# nRF2401A-Chip-v11.net
KiCad netlist of a schematic drawn in EAGLE
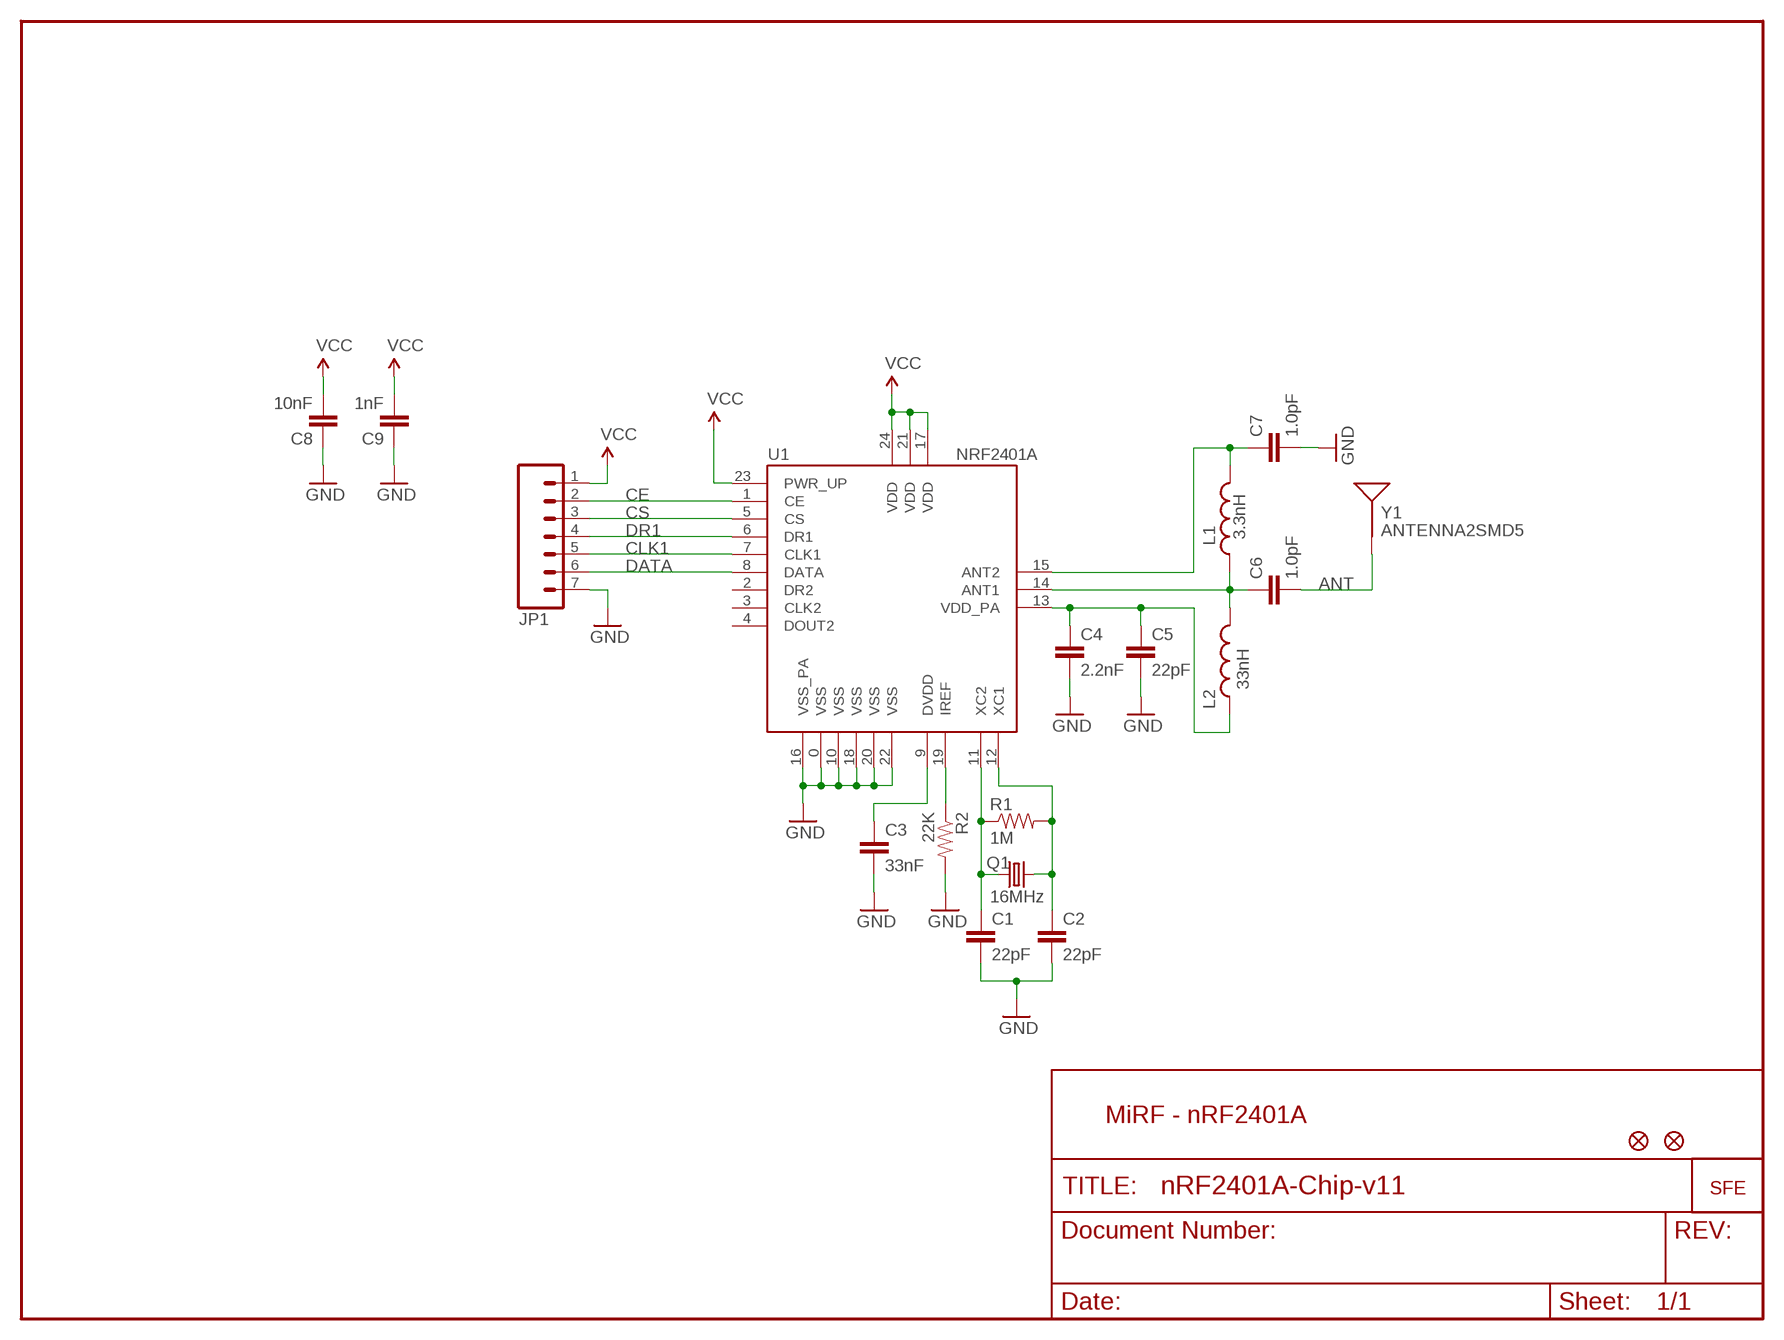
[diagram p0: schematic, sheet 1]

(export (version "E")
  (design (tool "Eeschema 10.0.6"))
  (components
    (comp (ref "C1")
      (value "22pF")
      (footprint "eagle-import:C0402")
      (libsource (lib "eagle-import") (part "CAP0402"))
    )
    (comp (ref "C2")
      (value "22pF")
      (footprint "eagle-import:C0402")
      (libsource (lib "eagle-import") (part "CAP0402"))
    )
    (comp (ref "C3")
      (value "33nF")
      (footprint "eagle-import:C0402")
      (libsource (lib "eagle-import") (part "CAP0402"))
    )
    (comp (ref "C4")
      (value "2.2nF")
      (footprint "eagle-import:C0402")
      (libsource (lib "eagle-import") (part "CAP0402"))
    )
    (comp (ref "C5")
      (value "22pF")
      (footprint "eagle-import:C0402")
      (libsource (lib "eagle-import") (part "CAP0402"))
    )
    (comp (ref "C6")
      (value "1.0pF")
      (footprint "eagle-import:C0402")
      (libsource (lib "eagle-import") (part "CAP0402"))
    )
    (comp (ref "C7")
      (value "1.0pF")
      (footprint "eagle-import:C0402")
      (libsource (lib "eagle-import") (part "CAP0402"))
    )
    (comp (ref "C8")
      (value "10nF")
      (footprint "eagle-import:C0402")
      (libsource (lib "eagle-import") (part "CAP0402"))
    )
    (comp (ref "C9")
      (value "1nF")
      (footprint "eagle-import:C0402")
      (libsource (lib "eagle-import") (part "CAP0402"))
    )
    (comp (ref "JP1")
      (value "M07")
      (footprint "eagle-import:1X07")
      (libsource (lib "eagle-import") (part "M07"))
    )
    (comp (ref "JP2")
      (value "FIDUCIALUFIDUCIAL")
      (footprint "eagle-import:MICRO-FIDUCIAL")
      (libsource (lib "eagle-import") (part "FIDUCIALUFIDUCIAL"))
    )
    (comp (ref "JP3")
      (value "FIDUCIALUFIDUCIAL")
      (footprint "eagle-import:MICRO-FIDUCIAL")
      (libsource (lib "eagle-import") (part "FIDUCIALUFIDUCIAL"))
    )
    (comp (ref "L1")
      (value "3.3nH")
      (footprint "eagle-import:C0402")
      (libsource (lib "eagle-import") (part "INDUCTOR0402"))
    )
    (comp (ref "L2")
      (value "33nH")
      (footprint "eagle-import:C0402")
      (libsource (lib "eagle-import") (part "INDUCTOR0402"))
    )
    (comp (ref "Q1")
      (value "16MHz")
      (footprint "eagle-import:CRYSTAL-SMD-5X3")
      (libsource (lib "eagle-import") (part "CRYSTAL5X3"))
    )
    (comp (ref "R1")
      (value "1M")
      (footprint "eagle-import:C0402")
      (libsource (lib "eagle-import") (part "RESISTOR0402"))
    )
    (comp (ref "R2")
      (value "22K")
      (footprint "eagle-import:C0402")
      (libsource (lib "eagle-import") (part "RESISTOR0402"))
    )
    (comp (ref "U$1")
      (value "LOGO-SFESK")
      (footprint "eagle-import:SFE-LOGO-FLAME")
      (libsource (lib "eagle-import") (part "LOGO-SFESK"))
    )
    (comp (ref "U1")
      (value "NRF2401A")
      (footprint "eagle-import:MLP-24")
      (libsource (lib "eagle-import") (part "NRF2401ASMD"))
    )
    (comp (ref "Y1")
      (value "ANTENNA2SMD5")
      (footprint "eagle-import:ANTENNA-CHIP5")
      (libsource (lib "eagle-import") (part "ANTENNA2SMD5"))
    )
  )
  (nets
    (net (code "1") (name "/ANT") (class "Default")
      (node (ref "C6") (pin "2") (pinfunction "2_2") (pintype "passive"))
      (node (ref "Y1") (pin "FEED") (pinfunction "SIGNAL_FEED") (pintype "bidirectional"))
    )
    (net (code "2") (name "/CE") (class "Default")
      (node (ref "JP1") (pin "2") (pinfunction "2_2") (pintype "passive"))
      (node (ref "U1") (pin "1") (pinfunction "CE_1") (pintype "input"))
    )
    (net (code "3") (name "/CLK1") (class "Default")
      (node (ref "JP1") (pin "5") (pinfunction "5_5") (pintype "passive"))
      (node (ref "U1") (pin "7") (pinfunction "CLK1_7") (pintype "bidirectional"))
    )
    (net (code "4") (name "/CS") (class "Default")
      (node (ref "JP1") (pin "3") (pinfunction "3_3") (pintype "passive"))
      (node (ref "U1") (pin "5") (pinfunction "CS_5") (pintype "input"))
    )
    (net (code "5") (name "/DATA") (class "Default")
      (node (ref "JP1") (pin "6") (pinfunction "6_6") (pintype "passive"))
      (node (ref "U1") (pin "8") (pinfunction "DATA_8") (pintype "bidirectional"))
    )
    (net (code "6") (name "/DR1") (class "Default")
      (node (ref "JP1") (pin "4") (pinfunction "4_4") (pintype "passive"))
      (node (ref "U1") (pin "6") (pinfunction "DR1_6") (pintype "output"))
    )
    (net (code "7") (name "GND") (class "Default")
      (node (ref "C1") (pin "2") (pinfunction "2_2") (pintype "passive"))
      (node (ref "C2") (pin "2") (pinfunction "2_2") (pintype "passive"))
      (node (ref "C3") (pin "2") (pinfunction "2_2") (pintype "passive"))
      (node (ref "C4") (pin "2") (pinfunction "2_2") (pintype "passive"))
      (node (ref "C5") (pin "2") (pinfunction "2_2") (pintype "passive"))
      (node (ref "C7") (pin "2") (pinfunction "2_2") (pintype "passive"))
      (node (ref "C8") (pin "1") (pinfunction "1_1") (pintype "passive"))
      (node (ref "C9") (pin "1") (pinfunction "1_1") (pintype "passive"))
      (node (ref "JP1") (pin "7") (pinfunction "7_7") (pintype "passive"))
      (node (ref "R2") (pin "2") (pinfunction "2_2") (pintype "passive"))
      (node (ref "U1") (pin "0") (pinfunction "VSS_0") (pintype "power_in"))
      (node (ref "U1") (pin "10") (pinfunction "VSS_10") (pintype "power_in"))
      (node (ref "U1") (pin "16") (pinfunction "VSS_PA_16") (pintype "power_in"))
      (node (ref "U1") (pin "18") (pinfunction "VSS_18") (pintype "power_in"))
      (node (ref "U1") (pin "20") (pinfunction "VSS_20") (pintype "power_in"))
      (node (ref "U1") (pin "22") (pinfunction "VSS_22") (pintype "power_in"))
    )
    (net (code "8") (name "Net-(Q1-2)") (class "Default")
      (node (ref "C2") (pin "1") (pinfunction "1_1") (pintype "passive"))
      (node (ref "Q1") (pin "3") (pinfunction "2_3") (pintype "passive"))
      (node (ref "R1") (pin "2") (pinfunction "2_2") (pintype "passive"))
      (node (ref "U1") (pin "12") (pinfunction "XC1_12") (pintype "input"))
    )
    (net (code "9") (name "Net-(U1-ANT1)") (class "Default")
      (node (ref "C6") (pin "1") (pinfunction "1_1") (pintype "passive"))
      (node (ref "L1") (pin "1") (pinfunction "1_1") (pintype "passive"))
      (node (ref "L2") (pin "2") (pinfunction "2_2") (pintype "passive"))
      (node (ref "U1") (pin "14") (pinfunction "ANT1_14") (pintype "output"))
    )
    (net (code "10") (name "Net-(U1-ANT2)") (class "Default")
      (node (ref "C7") (pin "1") (pinfunction "1_1") (pintype "passive"))
      (node (ref "L1") (pin "2") (pinfunction "2_2") (pintype "passive"))
      (node (ref "U1") (pin "15") (pinfunction "ANT2_15") (pintype "output"))
    )
    (net (code "11") (name "Net-(U1-DVDD)") (class "Default")
      (node (ref "C3") (pin "1") (pinfunction "1_1") (pintype "passive"))
      (node (ref "U1") (pin "9") (pinfunction "DVDD_9") (pintype "power_in"))
    )
    (net (code "12") (name "Net-(U1-IREF)") (class "Default")
      (node (ref "R2") (pin "1") (pinfunction "1_1") (pintype "passive"))
      (node (ref "U1") (pin "19") (pinfunction "IREF_19") (pintype "input"))
    )
    (net (code "13") (name "Net-(U1-VDD_PA)") (class "Default")
      (node (ref "C4") (pin "1") (pinfunction "1_1") (pintype "passive"))
      (node (ref "C5") (pin "1") (pinfunction "1_1") (pintype "passive"))
      (node (ref "L2") (pin "1") (pinfunction "1_1") (pintype "passive"))
      (node (ref "U1") (pin "13") (pinfunction "VDD_PA_13") (pintype "power_in"))
    )
    (net (code "14") (name "Net-(U1-XC2)") (class "Default")
      (node (ref "C1") (pin "1") (pinfunction "1_1") (pintype "passive"))
      (node (ref "Q1") (pin "1") (pinfunction "1_1") (pintype "passive"))
      (node (ref "R1") (pin "1") (pinfunction "1_1") (pintype "passive"))
      (node (ref "U1") (pin "11") (pinfunction "XC2_11") (pintype "input"))
    )
    (net (code "15") (name "VCC") (class "Default")
      (node (ref "C8") (pin "2") (pinfunction "2_2") (pintype "passive"))
      (node (ref "C9") (pin "2") (pinfunction "2_2") (pintype "passive"))
      (node (ref "JP1") (pin "1") (pinfunction "1_1") (pintype "passive"))
      (node (ref "U1") (pin "17") (pinfunction "VDD_17") (pintype "power_in"))
      (node (ref "U1") (pin "21") (pinfunction "VDD_21") (pintype "power_in"))
      (node (ref "U1") (pin "23") (pinfunction "PWR_UP_23") (pintype "power_in"))
      (node (ref "U1") (pin "24") (pinfunction "VDD_24") (pintype "power_in"))
    )
    (net (code "16") (name "unconnected-(U1-CLK2-Pad3)") (class "Default")
      (node (ref "U1") (pin "3") (pinfunction "CLK2_3") (pintype "bidirectional"))
    )
    (net (code "17") (name "unconnected-(U1-DOUT2-Pad4)") (class "Default")
      (node (ref "U1") (pin "4") (pinfunction "DOUT2_4") (pintype "output"))
    )
    (net (code "18") (name "unconnected-(U1-DR2-Pad2)") (class "Default")
      (node (ref "U1") (pin "2") (pinfunction "DR2_2") (pintype "output"))
    )
  )
)
